# Power_LoadSwitches.net
KiCad netlist of a schematic drawn in Altium Designer
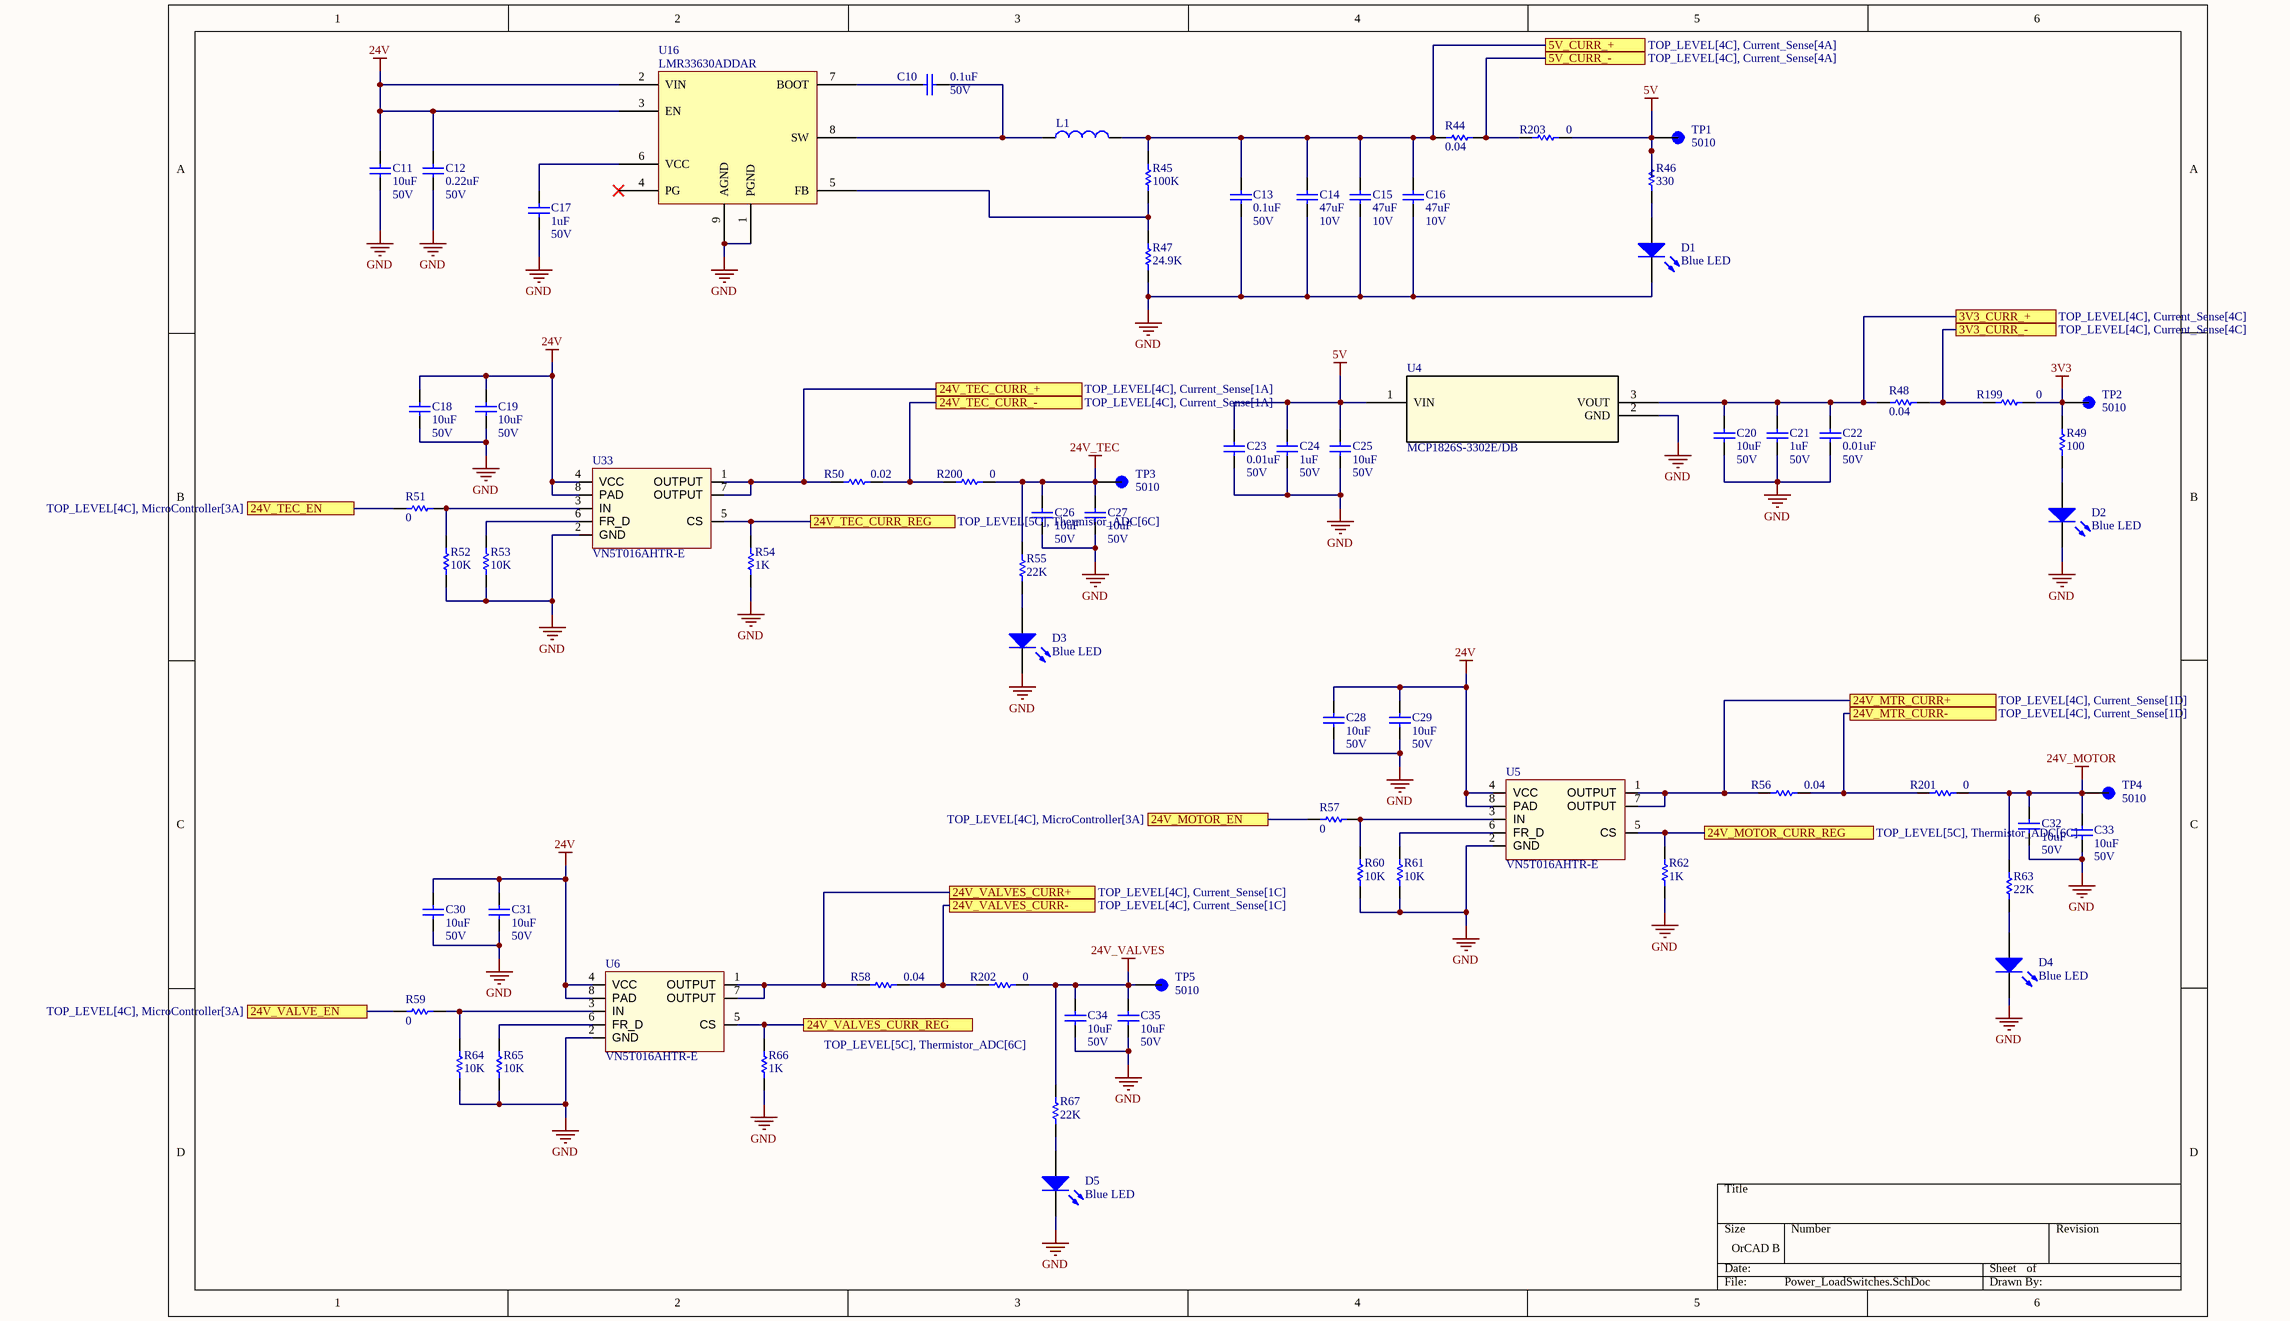
[diagram p0: Power_LoadSwitches.SchDoc]

(export (version "E")
  (design (tool "Eeschema 10.0.6"))
  (components
    (comp (ref "C10")
      (value "0.1uF")
      (footprint "DEFAULT_CAPACITOR_0805")
      (description "CAP CER 0.1UF 50V X7R 0805")
      (fields
        (field (name "MANUFACTURER") "Cal-Chip Electronics, Inc.")
        (field (name "RATING") "50V")
        (field (name "Comment") "KGM21NR71H104KT")
      )
      (libsource (lib "Avery Altium Llibrary") (part "KGM21NR71H104KT"))
    )
    (comp (ref "C11")
      (value "10uF")
      (footprint "DEFAULT_CAPACITOR_0805")
      (description "CAP CER 10UF 50V X5R 0805")
      (fields (field (name "RATING") "50V") (field (name "Comment") "GRM21BR61H106KE43L"))
      (libsource (lib "Avery Altium Llibrary") (part "GRM21BR61H106KE43L"))
    )
    (comp (ref "C12")
      (value "0.22uF")
      (footprint "DEFAULT_CAPACITOR_0805")
      (description "CAP CER 0.22UF 50V X7R 0805")
      (fields (field (name "RATING") "50V") (field (name "Comment") "C0805C224K5RACTU"))
      (libsource (lib "Avery Altium Llibrary") (part "C0805C224K5RACTU"))
    )
    (comp (ref "C13")
      (value "0.1uF")
      (footprint "DEFAULT_CAPACITOR_0805")
      (description "CAP CER 0.1UF 50V X7R 0805")
      (fields
        (field (name "MANUFACTURER") "Cal-Chip Electronics, Inc.")
        (field (name "RATING") "50V")
        (field (name "Comment") "KGM21NR71H104KT")
      )
      (libsource (lib "Avery Altium Llibrary") (part "KGM21NR71H104KT"))
    )
    (comp (ref "C14")
      (value "47uF")
      (footprint "DEFAULT_CAPACITOR_0805")
      (description "CAP CER 47UF 10V X5R 0805")
      (fields (field (name "RATING") "10V") (field (name "Comment") "GRM21BR61A476ME15L"))
      (libsource (lib "Avery Altium Llibrary") (part "GRM21BR61A476ME15L"))
    )
    (comp (ref "C15")
      (value "47uF")
      (footprint "DEFAULT_CAPACITOR_0805")
      (description "CAP CER 47UF 10V X5R 0805")
      (fields (field (name "RATING") "10V") (field (name "Comment") "GRM21BR61A476ME15L"))
      (libsource (lib "Avery Altium Llibrary") (part "GRM21BR61A476ME15L"))
    )
    (comp (ref "C16")
      (value "47uF")
      (footprint "DEFAULT_CAPACITOR_0805")
      (description "CAP CER 47UF 10V X5R 0805")
      (fields (field (name "RATING") "10V") (field (name "Comment") "GRM21BR61A476ME15L"))
      (libsource (lib "Avery Altium Llibrary") (part "GRM21BR61A476ME15L"))
    )
    (comp (ref "C17")
      (value "1uF")
      (footprint "DEFAULT_CAPACITOR_0805")
      (description "CAP CER 1UF 50V X7R 0805")
      (fields (field (name "RATING") "50V") (field (name "Comment") "CL21B105KBFNNNE"))
      (libsource (lib "Avery Altium Llibrary") (part "CL21B105KBFNNNE"))
    )
    (comp (ref "C18")
      (value "10uF")
      (footprint "DEFAULT_CAPACITOR_0805")
      (description "CAP CER 10UF 50V X5R 0805")
      (fields (field (name "RATING") "50V") (field (name "Comment") "GRM21BR61H106KE43L"))
      (libsource (lib "Avery Altium Llibrary") (part "GRM21BR61H106KE43L"))
    )
    (comp (ref "C19")
      (value "10uF")
      (footprint "DEFAULT_CAPACITOR_0805")
      (description "CAP CER 10UF 50V X5R 0805")
      (fields (field (name "RATING") "50V") (field (name "Comment") "GRM21BR61H106KE43L"))
      (libsource (lib "Avery Altium Llibrary") (part "GRM21BR61H106KE43L"))
    )
    (comp (ref "C20")
      (value "10uF")
      (footprint "DEFAULT_CAPACITOR_0805")
      (description "CAP CER 10UF 50V X5R 0805")
      (fields (field (name "RATING") "50V") (field (name "Comment") "GRM21BR61H106KE43L"))
      (libsource (lib "Avery Altium Llibrary") (part "GRM21BR61H106KE43L"))
    )
    (comp (ref "C21")
      (value "1uF")
      (footprint "DEFAULT_CAPACITOR_0805")
      (description "CAP CER 1UF 50V X7R 0805")
      (fields (field (name "RATING") "50V") (field (name "Comment") "CL21B105KBFNNNE"))
      (libsource (lib "Avery Altium Llibrary") (part "CL21B105KBFNNNE"))
    )
    (comp (ref "C22")
      (value "0.01uF")
      (footprint "DEFAULT_CAPACITOR_0805")
      (description "CAP CER 10000PF 50V X7R 0805")
      (fields
        (field (name "MANUFACTURER") "Cal-Chip Electronics, Inc.")
        (field (name "RATING") "50V")
        (field (name "Comment") "KGM21NR71H103KT")
      )
      (libsource (lib "Avery Altium Llibrary") (part "KGM21NR71H103KT"))
    )
    (comp (ref "C23")
      (value "0.01uF")
      (footprint "DEFAULT_CAPACITOR_0805")
      (description "CAP CER 10000PF 50V X7R 0805")
      (fields
        (field (name "MANUFACTURER") "Cal-Chip Electronics, Inc.")
        (field (name "RATING") "50V")
        (field (name "Comment") "KGM21NR71H103KT")
      )
      (libsource (lib "Avery Altium Llibrary") (part "KGM21NR71H103KT"))
    )
    (comp (ref "C24")
      (value "1uF")
      (footprint "DEFAULT_CAPACITOR_0805")
      (description "CAP CER 1UF 50V X7R 0805")
      (fields (field (name "RATING") "50V") (field (name "Comment") "CL21B105KBFNNNE"))
      (libsource (lib "Avery Altium Llibrary") (part "CL21B105KBFNNNE"))
    )
    (comp (ref "C25")
      (value "10uF")
      (footprint "DEFAULT_CAPACITOR_0805")
      (description "CAP CER 10UF 50V X5R 0805")
      (fields (field (name "RATING") "50V") (field (name "Comment") "GRM21BR61H106KE43L"))
      (libsource (lib "Avery Altium Llibrary") (part "GRM21BR61H106KE43L"))
    )
    (comp (ref "C26")
      (value "10uF")
      (footprint "DEFAULT_CAPACITOR_0805")
      (description "CAP CER 10UF 50V X5R 0805")
      (fields (field (name "RATING") "50V") (field (name "Comment") "GRM21BR61H106KE43L"))
      (libsource (lib "Avery Altium Llibrary") (part "GRM21BR61H106KE43L"))
    )
    (comp (ref "C27")
      (value "10uF")
      (footprint "DEFAULT_CAPACITOR_0805")
      (description "CAP CER 10UF 50V X5R 0805")
      (fields (field (name "RATING") "50V") (field (name "Comment") "GRM21BR61H106KE43L"))
      (libsource (lib "Avery Altium Llibrary") (part "GRM21BR61H106KE43L"))
    )
    (comp (ref "C28")
      (value "10uF")
      (footprint "DEFAULT_CAPACITOR_0805")
      (description "CAP CER 10UF 50V X5R 0805")
      (fields (field (name "RATING") "50V") (field (name "Comment") "GRM21BR61H106KE43L"))
      (libsource (lib "Avery Altium Llibrary") (part "GRM21BR61H106KE43L"))
    )
    (comp (ref "C29")
      (value "10uF")
      (footprint "DEFAULT_CAPACITOR_0805")
      (description "CAP CER 10UF 50V X5R 0805")
      (fields (field (name "RATING") "50V") (field (name "Comment") "GRM21BR61H106KE43L"))
      (libsource (lib "Avery Altium Llibrary") (part "GRM21BR61H106KE43L"))
    )
    (comp (ref "C30")
      (value "10uF")
      (footprint "DEFAULT_CAPACITOR_0805")
      (description "CAP CER 10UF 50V X5R 0805")
      (fields (field (name "RATING") "50V") (field (name "Comment") "GRM21BR61H106KE43L"))
      (libsource (lib "Avery Altium Llibrary") (part "GRM21BR61H106KE43L"))
    )
    (comp (ref "C31")
      (value "10uF")
      (footprint "DEFAULT_CAPACITOR_0805")
      (description "CAP CER 10UF 50V X5R 0805")
      (fields (field (name "RATING") "50V") (field (name "Comment") "GRM21BR61H106KE43L"))
      (libsource (lib "Avery Altium Llibrary") (part "GRM21BR61H106KE43L"))
    )
    (comp (ref "C32")
      (value "10uF")
      (footprint "DEFAULT_CAPACITOR_0805")
      (description "CAP CER 10UF 50V X5R 0805")
      (fields (field (name "RATING") "50V") (field (name "Comment") "GRM21BR61H106KE43L"))
      (libsource (lib "Avery Altium Llibrary") (part "GRM21BR61H106KE43L"))
    )
    (comp (ref "C33")
      (value "10uF")
      (footprint "DEFAULT_CAPACITOR_0805")
      (description "CAP CER 10UF 50V X5R 0805")
      (fields (field (name "RATING") "50V") (field (name "Comment") "GRM21BR61H106KE43L"))
      (libsource (lib "Avery Altium Llibrary") (part "GRM21BR61H106KE43L"))
    )
    (comp (ref "C34")
      (value "10uF")
      (footprint "DEFAULT_CAPACITOR_0805")
      (description "CAP CER 10UF 50V X5R 0805")
      (fields (field (name "RATING") "50V") (field (name "Comment") "GRM21BR61H106KE43L"))
      (libsource (lib "Avery Altium Llibrary") (part "GRM21BR61H106KE43L"))
    )
    (comp (ref "C35")
      (value "10uF")
      (footprint "DEFAULT_CAPACITOR_0805")
      (description "CAP CER 10UF 50V X5R 0805")
      (fields (field (name "RATING") "50V") (field (name "Comment") "GRM21BR61H106KE43L"))
      (libsource (lib "Avery Altium Llibrary") (part "GRM21BR61H106KE43L"))
    )
    (comp (ref "D1")
      (value "Blue LED")
      (footprint "DEFAULT_RESISTOR_0805")
      (description "LED BLUE")
      (fields (field (name "MP") "Blue LED 0805") (field (name "Comment") "LSM0805463V"))
      (libsource (lib "Avery Altium Llibrary") (part "LSM0805463V"))
    )
    (comp (ref "D2")
      (value "Blue LED")
      (footprint "DEFAULT_RESISTOR_0805")
      (description "LED BLUE")
      (fields (field (name "MP") "Blue LED 0805") (field (name "Comment") "LSM0805463V"))
      (libsource (lib "Avery Altium Llibrary") (part "LSM0805463V"))
    )
    (comp (ref "D3")
      (value "Blue LED")
      (footprint "DEFAULT_RESISTOR_0805")
      (description "LED BLUE")
      (fields (field (name "MP") "Blue LED 0805") (field (name "Comment") "LSM0805463V"))
      (libsource (lib "Avery Altium Llibrary") (part "LSM0805463V"))
    )
    (comp (ref "D4")
      (value "Blue LED")
      (footprint "DEFAULT_RESISTOR_0805")
      (description "LED BLUE")
      (fields (field (name "MP") "Blue LED 0805") (field (name "Comment") "LSM0805463V"))
      (libsource (lib "Avery Altium Llibrary") (part "LSM0805463V"))
    )
    (comp (ref "D5")
      (value "Blue LED")
      (footprint "DEFAULT_RESISTOR_0805")
      (description "LED BLUE")
      (fields (field (name "MP") "Blue LED 0805") (field (name "Comment") "LSM0805463V"))
      (libsource (lib "Avery Altium Llibrary") (part "LSM0805463V"))
    )
    (comp (ref "L1")
      (value "744771008")
      (footprint "744771008")
      (description "FIXED IND 8.2UH 6.25A 20 MOHM")
      (libsource (lib "Avery Altium Llibrary") (part "744771008"))
    )
    (comp (ref "R44")
      (value "0.04")
      (footprint "DEFAULT_RESISTOR_0805")
      (description "RES 0.04 OHM 0.5% 1/2W 0805")
      (fields (field (name "POWER") "1/2W") (field (name "TOLERANCE") "0.5%"))
      (libsource (lib "Avery Altium Llibrary") (part "WSLP0805R0400DEA"))
    )
    (comp (ref "R45")
      (value "100K")
      (footprint "DEFAULT_RESISTOR_0805")
      (description "RES 100K OHM 1% 1/8W 0805")
      (fields (field (name "POWER") "1/8W") (field (name "TOLERANCE") "1%"))
      (libsource (lib "Avery Altium Llibrary") (part "RC0805FR-07100KL"))
    )
    (comp (ref "R46")
      (value "330")
      (footprint "DEFAULT_RESISTOR_0805")
      (description "RES 330 OHM 1% 1/8W 0805")
      (fields (field (name "TOLERANCE") "1%") (field (name "Comment") "RMCF0805FT330R"))
      (libsource (lib "Avery Altium Llibrary") (part "RMCF0805FT330R"))
    )
    (comp (ref "R47")
      (value "24.9K")
      (footprint "DEFAULT_RESISTOR_0805")
      (description "RES 24.9K OHM 1% 1/8W 0805")
      (fields (field (name "POWER") "1/8W") (field (name "TOLERANCE") "1%"))
      (libsource (lib "Avery Altium Llibrary") (part "RMCF0805FT24K9"))
    )
    (comp (ref "R48")
      (value "0.04")
      (footprint "DEFAULT_RESISTOR_0805")
      (description "RES 0.04 OHM 0.5% 1/2W 0805")
      (fields (field (name "POWER") "1/2W") (field (name "TOLERANCE") "0.5%"))
      (libsource (lib "Avery Altium Llibrary") (part "WSLP0805R0400DEA"))
    )
    (comp (ref "R49")
      (value "100")
      (footprint "DEFAULT_RESISTOR_0805")
      (description "RES SMD 100 OHM 1% 1/4W 0805")
      (fields (field (name "POWER") "1/4W") (field (name "TOLERANCE") "1%"))
      (libsource (lib "Avery Altium Llibrary") (part "CRCW0805100RFKEA"))
    )
    (comp (ref "R50")
      (value "0.02")
      (footprint "DEFAULT_RESISTOR_0805")
      (description "RES 0.02 OHM 0.5% 1/2W 0805")
      (fields (field (name "POWER") "1/2W") (field (name "TOLERANCE") "0.5%"))
      (libsource (lib "Avery Altium Llibrary") (part "ERJ-6CWDR020V"))
    )
    (comp (ref "R51")
      (value "0")
      (footprint "DEFAULT_RESISTOR_0805")
      (description "RES 0 OHM JUMPER 1/8W 0805")
      (fields (field (name "POWER") "1/8W") (field (name "Comment") "RC0805JR-070RL"))
      (libsource (lib "Avery Altium Llibrary") (part "RC0805JR-070RL"))
    )
    (comp (ref "R52")
      (value "10K")
      (footprint "DEFAULT_RESISTOR_0805")
      (description "RES SMD 10K OHM 1% 1/4W 0805")
      (fields (field (name "POWER") "1/4W") (field (name "TOLERANCE") "1%"))
      (libsource (lib "Avery Altium Llibrary") (part "CRCW080510K0FKEA"))
    )
    (comp (ref "R53")
      (value "10K")
      (footprint "DEFAULT_RESISTOR_0805")
      (description "RES SMD 10K OHM 1% 1/4W 0805")
      (fields (field (name "POWER") "1/4W") (field (name "TOLERANCE") "1%"))
      (libsource (lib "Avery Altium Llibrary") (part "CRCW080510K0FKEA"))
    )
    (comp (ref "R54")
      (value "1K")
      (footprint "DEFAULT_RESISTOR_0805")
      (description "RES SMD 1K OHM 1% 1/4W 0805")
      (fields (field (name "POWER") "1/4W") (field (name "TOLERANCE") "1%"))
      (libsource (lib "Avery Altium Llibrary") (part "CRCW08051K00FKEA"))
    )
    (comp (ref "R55")
      (value "22K")
      (footprint "DEFAULT_RESISTOR_0805")
      (description "RES 22K OHM 1% 1/8W 0805")
      (fields (field (name "POWER") "1/8W") (field (name "TOLERANCE") "1%"))
      (libsource (lib "Avery Altium Llibrary") (part "RC0805FR-1322KL"))
    )
    (comp (ref "R56")
      (value "0.04")
      (footprint "DEFAULT_RESISTOR_0805")
      (description "RES 0.04 OHM 0.5% 1/2W 0805")
      (fields (field (name "POWER") "1/2W") (field (name "TOLERANCE") "0.5%"))
      (libsource (lib "Avery Altium Llibrary") (part "WSLP0805R0400DEA"))
    )
    (comp (ref "R57")
      (value "0")
      (footprint "DEFAULT_RESISTOR_0805")
      (description "RES 0 OHM JUMPER 1/8W 0805")
      (fields (field (name "POWER") "1/8W") (field (name "Comment") "RC0805JR-070RL"))
      (libsource (lib "Avery Altium Llibrary") (part "RC0805JR-070RL"))
    )
    (comp (ref "R58")
      (value "0.04")
      (footprint "DEFAULT_RESISTOR_0805")
      (description "RES 0.04 OHM 0.5% 1/2W 0805")
      (fields (field (name "POWER") "1/2W") (field (name "TOLERANCE") "0.5%"))
      (libsource (lib "Avery Altium Llibrary") (part "WSLP0805R0400DEA"))
    )
    (comp (ref "R59")
      (value "0")
      (footprint "DEFAULT_RESISTOR_0805")
      (description "RES 0 OHM JUMPER 1/8W 0805")
      (fields (field (name "POWER") "1/8W") (field (name "Comment") "RC0805JR-070RL"))
      (libsource (lib "Avery Altium Llibrary") (part "RC0805JR-070RL"))
    )
    (comp (ref "R60")
      (value "10K")
      (footprint "DEFAULT_RESISTOR_0805")
      (description "RES SMD 10K OHM 1% 1/4W 0805")
      (fields (field (name "POWER") "1/4W") (field (name "TOLERANCE") "1%"))
      (libsource (lib "Avery Altium Llibrary") (part "CRCW080510K0FKEA"))
    )
    (comp (ref "R61")
      (value "10K")
      (footprint "DEFAULT_RESISTOR_0805")
      (description "RES SMD 10K OHM 1% 1/4W 0805")
      (fields (field (name "POWER") "1/4W") (field (name "TOLERANCE") "1%"))
      (libsource (lib "Avery Altium Llibrary") (part "CRCW080510K0FKEA"))
    )
    (comp (ref "R62")
      (value "1K")
      (footprint "DEFAULT_RESISTOR_0805")
      (description "RES SMD 1K OHM 1% 1/4W 0805")
      (fields (field (name "POWER") "1/4W") (field (name "TOLERANCE") "1%"))
      (libsource (lib "Avery Altium Llibrary") (part "CRCW08051K00FKEA"))
    )
    (comp (ref "R63")
      (value "22K")
      (footprint "DEFAULT_RESISTOR_0805")
      (description "RES 22K OHM 1% 1/8W 0805")
      (fields (field (name "POWER") "1/8W") (field (name "TOLERANCE") "1%"))
      (libsource (lib "Avery Altium Llibrary") (part "RC0805FR-1322KL"))
    )
    (comp (ref "R64")
      (value "10K")
      (footprint "DEFAULT_RESISTOR_0805")
      (description "RES SMD 10K OHM 1% 1/4W 0805")
      (fields (field (name "POWER") "1/4W") (field (name "TOLERANCE") "1%"))
      (libsource (lib "Avery Altium Llibrary") (part "CRCW080510K0FKEA"))
    )
    (comp (ref "R65")
      (value "10K")
      (footprint "DEFAULT_RESISTOR_0805")
      (description "RES SMD 10K OHM 1% 1/4W 0805")
      (fields (field (name "POWER") "1/4W") (field (name "TOLERANCE") "1%"))
      (libsource (lib "Avery Altium Llibrary") (part "CRCW080510K0FKEA"))
    )
    (comp (ref "R66")
      (value "1K")
      (footprint "DEFAULT_RESISTOR_0805")
      (description "RES SMD 1K OHM 1% 1/4W 0805")
      (fields (field (name "POWER") "1/4W") (field (name "TOLERANCE") "1%"))
      (libsource (lib "Avery Altium Llibrary") (part "CRCW08051K00FKEA"))
    )
    (comp (ref "R67")
      (value "22K")
      (footprint "DEFAULT_RESISTOR_0805")
      (description "RES 22K OHM 1% 1/8W 0805")
      (fields (field (name "POWER") "1/8W") (field (name "TOLERANCE") "1%"))
      (libsource (lib "Avery Altium Llibrary") (part "RC0805FR-1322KL"))
    )
    (comp (ref "R199")
      (value "0")
      (footprint "DEFAULT_RESISTOR_0805")
      (description "RES 0 OHM JUMPER 1/8W 0805")
      (fields (field (name "POWER") "1/8W") (field (name "Comment") "RC0805JR-070RL"))
      (libsource (lib "Avery Altium Llibrary") (part "RC0805JR-070RL"))
    )
    (comp (ref "R200")
      (value "0")
      (footprint "DEFAULT_RESISTOR_0805")
      (description "RES 0 OHM JUMPER 1/8W 0805")
      (fields (field (name "POWER") "1/8W") (field (name "Comment") "RC0805JR-070RL"))
      (libsource (lib "Avery Altium Llibrary") (part "RC0805JR-070RL"))
    )
    (comp (ref "R201")
      (value "0")
      (footprint "DEFAULT_RESISTOR_0805")
      (description "RES 0 OHM JUMPER 1/8W 0805")
      (fields (field (name "POWER") "1/8W") (field (name "Comment") "RC0805JR-070RL"))
      (libsource (lib "Avery Altium Llibrary") (part "RC0805JR-070RL"))
    )
    (comp (ref "R202")
      (value "0")
      (footprint "DEFAULT_RESISTOR_0805")
      (description "RES 0 OHM JUMPER 1/8W 0805")
      (fields (field (name "POWER") "1/8W") (field (name "Comment") "RC0805JR-070RL"))
      (libsource (lib "Avery Altium Llibrary") (part "RC0805JR-070RL"))
    )
    (comp (ref "R203")
      (value "0")
      (footprint "DEFAULT_RESISTOR_0805")
      (description "RES 0 OHM JUMPER 1/8W 0805")
      (fields (field (name "POWER") "1/8W") (field (name "Comment") "RC0805JR-070RL"))
      (libsource (lib "Avery Altium Llibrary") (part "RC0805JR-070RL"))
    )
    (comp (ref "TP1")
      (value "5010")
      (footprint "TP_5011")
      (description "PC TEST POINT MULTIPURPOSE RED")
      (libsource (lib "Avery Altium Llibrary") (part "5010"))
    )
    (comp (ref "TP2")
      (value "5010")
      (footprint "TP_5011")
      (description "PC TEST POINT MULTIPURPOSE RED")
      (libsource (lib "Avery Altium Llibrary") (part "5010"))
    )
    (comp (ref "TP3")
      (value "5010")
      (footprint "TP_5011")
      (description "PC TEST POINT MULTIPURPOSE RED")
      (libsource (lib "Avery Altium Llibrary") (part "5010"))
    )
    (comp (ref "TP4")
      (value "5010")
      (footprint "TP_5011")
      (description "PC TEST POINT MULTIPURPOSE RED")
      (libsource (lib "Avery Altium Llibrary") (part "5010"))
    )
    (comp (ref "TP5")
      (value "5010")
      (footprint "TP_5011")
      (description "PC TEST POINT MULTIPURPOSE RED")
      (libsource (lib "Avery Altium Llibrary") (part "5010"))
    )
    (comp (ref "U4")
      (value "MCP1826S-3302E/DB")
      (footprint "MCP1826S-3302E/DB")
      (description "IC REG LINEAR 3.3V 1A SOT-223-3")
      (fields (field (name "COPYRIGHT") "Copyright (C) 2025 Ultra Librarian. All rights reserved."))
      (libsource (lib "Avery Altium Llibrary") (part "MCP1826S-3302E/DB"))
    )
    (comp (ref "U5")
      (value "VN5T016AHTR-E")
      (footprint "VN5T016AHTR-E-HPAK")
      (description "Power Switch/Driver 1:1 N-Channel 43A HPAK")
      (fields
        (field (name "MANUFACTURER") "STMicroelectronics")
        (field (name "MANUFACTURER P/N") "VN5T016AHTR-E")
      )
      (libsource (lib "Avery Schem Library") (part "VN5T016AHTR-E"))
    )
    (comp (ref "U6")
      (value "VN5T016AHTR-E")
      (footprint "VN5T016AHTR-E-HPAK")
      (description "Power Switch/Driver 1:1 N-Channel 43A HPAK")
      (fields
        (field (name "MANUFACTURER") "STMicroelectronics")
        (field (name "MANUFACTURER P/N") "VN5T016AHTR-E")
      )
      (libsource (lib "Avery Schem Library") (part "VN5T016AHTR-E"))
    )
    (comp (ref "U16")
      (value "LMR33630ADDAR")
      (footprint "VREG_LM5017MR/NOPB")
      (description "LMR33630 SIMPLE SWITCHER® 3.8-V to 36-V, 3-A\r\nSynchronous Step-down Voltage Converter")
      (fields (field (name "MP") "LMR33630ADDA") (field (name "DESIGNER") "OMIGA"))
      (libsource (lib "Avery Altium Llibrary") (part "LMR33630ADDAR"))
    )
    (comp (ref "U33")
      (value "VN5T016AHTR-E")
      (footprint "VN5T016AHTR-E-HPAK")
      (description "Power Switch/Driver 1:1 N-Channel 43A HPAK")
      (fields
        (field (name "MANUFACTURER") "STMicroelectronics")
        (field (name "MANUFACTURER P/N") "VN5T016AHTR-E")
      )
      (libsource (lib "Avery Schem Library") (part "VN5T016AHTR-E"))
    )
  )
  (nets
    (net (code "1") (name "/3V3_CURR_+") (class "Default")
      (node (ref "C20") (pin "2") (pinfunction "2_2") (pintype "passive"))
      (node (ref "C21") (pin "2") (pinfunction "2_2") (pintype "passive"))
      (node (ref "C22") (pin "2") (pinfunction "2_2") (pintype "passive"))
      (node (ref "R48") (pin "2") (pinfunction "2_2") (pintype "passive"))
      (node (ref "U4") (pin "3") (pinfunction "VOUT_3") (pintype "passive"))
    )
    (net (code "2") (name "/3V3_CURR_-") (class "Default")
      (node (ref "R199") (pin "2") (pinfunction "2_2") (pintype "passive"))
      (node (ref "R48") (pin "1") (pinfunction "1_1") (pintype "passive"))
    )
    (net (code "3") (name "/5V_CURR_+") (class "Default")
      (node (ref "C13") (pin "2") (pinfunction "2_2") (pintype "passive"))
      (node (ref "C14") (pin "2") (pinfunction "2_2") (pintype "passive"))
      (node (ref "C15") (pin "2") (pinfunction "2_2") (pintype "passive"))
      (node (ref "C16") (pin "2") (pinfunction "2_2") (pintype "passive"))
      (node (ref "L1") (pin "2") (pinfunction "2_2") (pintype "passive"))
      (node (ref "R44") (pin "2") (pinfunction "2_2") (pintype "passive"))
      (node (ref "R45") (pin "1") (pinfunction "1_1") (pintype "passive"))
    )
    (net (code "4") (name "/5V_CURR_-") (class "Default")
      (node (ref "R203") (pin "2") (pinfunction "2_2") (pintype "passive"))
      (node (ref "R44") (pin "1") (pinfunction "1_1") (pintype "passive"))
    )
    (net (code "5") (name "/24V_MOTOR_CURR_REG") (class "Default")
      (node (ref "R62") (pin "1") (pinfunction "1_1") (pintype "passive"))
      (node (ref "U5") (pin "5") (pinfunction "CS_5") (pintype "passive"))
    )
    (net (code "6") (name "/24V_MOTOR_EN") (class "Default")
      (node (ref "R57") (pin "2") (pinfunction "2_2") (pintype "passive"))
    )
    (net (code "7") (name "/24V_MTR_CURR+") (class "Default")
      (node (ref "R56") (pin "2") (pinfunction "2_2") (pintype "passive"))
      (node (ref "U5") (pin "1") (pinfunction "OUTPUT_1") (pintype "passive"))
      (node (ref "U5") (pin "7") (pinfunction "OUTPUT_7") (pintype "passive"))
    )
    (net (code "8") (name "/24V_MTR_CURR-") (class "Default")
      (node (ref "R201") (pin "2") (pinfunction "2_2") (pintype "passive"))
      (node (ref "R56") (pin "1") (pinfunction "1_1") (pintype "passive"))
    )
    (net (code "9") (name "/24V_TEC_CURR_+") (class "Default")
      (node (ref "R50") (pin "2") (pinfunction "2_2") (pintype "passive"))
      (node (ref "U33") (pin "1") (pinfunction "OUTPUT_1") (pintype "passive"))
      (node (ref "U33") (pin "7") (pinfunction "OUTPUT_7") (pintype "passive"))
    )
    (net (code "10") (name "/24V_TEC_CURR_-") (class "Default")
      (node (ref "R200") (pin "2") (pinfunction "2_2") (pintype "passive"))
      (node (ref "R50") (pin "1") (pinfunction "1_1") (pintype "passive"))
    )
    (net (code "11") (name "/24V_TEC_CURR_REG") (class "Default")
      (node (ref "R54") (pin "1") (pinfunction "1_1") (pintype "passive"))
      (node (ref "U33") (pin "5") (pinfunction "CS_5") (pintype "passive"))
    )
    (net (code "12") (name "/24V_TEC_EN") (class "Default")
      (node (ref "R51") (pin "2") (pinfunction "2_2") (pintype "passive"))
    )
    (net (code "13") (name "/24V_VALVES_CURR+") (class "Default")
      (node (ref "R58") (pin "2") (pinfunction "2_2") (pintype "passive"))
      (node (ref "U6") (pin "1") (pinfunction "OUTPUT_1") (pintype "passive"))
      (node (ref "U6") (pin "7") (pinfunction "OUTPUT_7") (pintype "passive"))
    )
    (net (code "14") (name "/24V_VALVES_CURR-") (class "Default")
      (node (ref "R202") (pin "2") (pinfunction "2_2") (pintype "passive"))
      (node (ref "R58") (pin "1") (pinfunction "1_1") (pintype "passive"))
    )
    (net (code "15") (name "/24V_VALVES_CURR_REG") (class "Default")
      (node (ref "R66") (pin "1") (pinfunction "1_1") (pintype "passive"))
      (node (ref "U6") (pin "5") (pinfunction "CS_5") (pintype "passive"))
    )
    (net (code "16") (name "/24V_VALVE_EN") (class "Default")
      (node (ref "R59") (pin "2") (pinfunction "2_2") (pintype "passive"))
    )
    (net (code "17") (name "3V3") (class "Default")
      (node (ref "R199") (pin "1") (pinfunction "1_1") (pintype "passive"))
      (node (ref "R49") (pin "1") (pinfunction "1_1") (pintype "passive"))
      (node (ref "TP2") (pin "TP") (pinfunction "TP_TP") (pintype "passive"))
    )
    (net (code "18") (name "5V") (class "Default")
      (node (ref "C23") (pin "2") (pinfunction "2_2") (pintype "passive"))
      (node (ref "C24") (pin "2") (pinfunction "2_2") (pintype "passive"))
      (node (ref "C25") (pin "2") (pinfunction "2_2") (pintype "passive"))
      (node (ref "R203") (pin "1") (pinfunction "1_1") (pintype "passive"))
      (node (ref "R46") (pin "1") (pinfunction "1_1") (pintype "passive"))
      (node (ref "TP1") (pin "TP") (pinfunction "TP_TP") (pintype "passive"))
      (node (ref "U4") (pin "1") (pinfunction "VIN_1") (pintype "passive"))
    )
    (net (code "19") (name "24V") (class "Default")
      (node (ref "C11") (pin "2") (pinfunction "2_2") (pintype "passive"))
      (node (ref "C12") (pin "2") (pinfunction "2_2") (pintype "passive"))
      (node (ref "C18") (pin "2") (pinfunction "2_2") (pintype "passive"))
      (node (ref "C19") (pin "2") (pinfunction "2_2") (pintype "passive"))
      (node (ref "C28") (pin "2") (pinfunction "2_2") (pintype "passive"))
      (node (ref "C29") (pin "2") (pinfunction "2_2") (pintype "passive"))
      (node (ref "C30") (pin "2") (pinfunction "2_2") (pintype "passive"))
      (node (ref "C31") (pin "2") (pinfunction "2_2") (pintype "passive"))
      (node (ref "U16") (pin "2") (pinfunction "VIN_2") (pintype "power_in"))
      (node (ref "U16") (pin "3") (pinfunction "EN_3") (pintype "passive"))
      (node (ref "U33") (pin "4") (pinfunction "VCC_4") (pintype "passive"))
      (node (ref "U33") (pin "8") (pinfunction "PAD_8") (pintype "passive"))
      (node (ref "U5") (pin "4") (pinfunction "VCC_4") (pintype "passive"))
      (node (ref "U5") (pin "8") (pinfunction "PAD_8") (pintype "passive"))
      (node (ref "U6") (pin "4") (pinfunction "VCC_4") (pintype "passive"))
      (node (ref "U6") (pin "8") (pinfunction "PAD_8") (pintype "passive"))
    )
    (net (code "20") (name "24V_MOTOR") (class "Default")
      (node (ref "C32") (pin "2") (pinfunction "2_2") (pintype "passive"))
      (node (ref "C33") (pin "2") (pinfunction "2_2") (pintype "passive"))
      (node (ref "R201") (pin "1") (pinfunction "1_1") (pintype "passive"))
      (node (ref "R63") (pin "1") (pinfunction "1_1") (pintype "passive"))
      (node (ref "TP4") (pin "TP") (pinfunction "TP_TP") (pintype "passive"))
    )
    (net (code "21") (name "24V_TEC") (class "Default")
      (node (ref "C26") (pin "2") (pinfunction "2_2") (pintype "passive"))
      (node (ref "C27") (pin "2") (pinfunction "2_2") (pintype "passive"))
      (node (ref "R200") (pin "1") (pinfunction "1_1") (pintype "passive"))
      (node (ref "R55") (pin "1") (pinfunction "1_1") (pintype "passive"))
      (node (ref "TP3") (pin "TP") (pinfunction "TP_TP") (pintype "passive"))
    )
    (net (code "22") (name "24V_VALVES") (class "Default")
      (node (ref "C34") (pin "2") (pinfunction "2_2") (pintype "passive"))
      (node (ref "C35") (pin "2") (pinfunction "2_2") (pintype "passive"))
      (node (ref "R202") (pin "1") (pinfunction "1_1") (pintype "passive"))
      (node (ref "R67") (pin "1") (pinfunction "1_1") (pintype "passive"))
      (node (ref "TP5") (pin "TP") (pinfunction "TP_TP") (pintype "passive"))
    )
    (net (code "23") (name "GND") (class "Default")
      (node (ref "C11") (pin "1") (pinfunction "1_1") (pintype "passive"))
      (node (ref "C12") (pin "1") (pinfunction "1_1") (pintype "passive"))
      (node (ref "C13") (pin "1") (pinfunction "1_1") (pintype "passive"))
      (node (ref "C14") (pin "1") (pinfunction "1_1") (pintype "passive"))
      (node (ref "C15") (pin "1") (pinfunction "1_1") (pintype "passive"))
      (node (ref "C16") (pin "1") (pinfunction "1_1") (pintype "passive"))
      (node (ref "C17") (pin "1") (pinfunction "1_1") (pintype "passive"))
      (node (ref "C18") (pin "1") (pinfunction "1_1") (pintype "passive"))
      (node (ref "C19") (pin "1") (pinfunction "1_1") (pintype "passive"))
      (node (ref "C20") (pin "1") (pinfunction "1_1") (pintype "passive"))
      (node (ref "C21") (pin "1") (pinfunction "1_1") (pintype "passive"))
      (node (ref "C22") (pin "1") (pinfunction "1_1") (pintype "passive"))
      (node (ref "C23") (pin "1") (pinfunction "1_1") (pintype "passive"))
      (node (ref "C24") (pin "1") (pinfunction "1_1") (pintype "passive"))
      (node (ref "C25") (pin "1") (pinfunction "1_1") (pintype "passive"))
      (node (ref "C26") (pin "1") (pinfunction "1_1") (pintype "passive"))
      (node (ref "C27") (pin "1") (pinfunction "1_1") (pintype "passive"))
      (node (ref "C28") (pin "1") (pinfunction "1_1") (pintype "passive"))
      (node (ref "C29") (pin "1") (pinfunction "1_1") (pintype "passive"))
      (node (ref "C30") (pin "1") (pinfunction "1_1") (pintype "passive"))
      (node (ref "C31") (pin "1") (pinfunction "1_1") (pintype "passive"))
      (node (ref "C32") (pin "1") (pinfunction "1_1") (pintype "passive"))
      (node (ref "C33") (pin "1") (pinfunction "1_1") (pintype "passive"))
      (node (ref "C34") (pin "1") (pinfunction "1_1") (pintype "passive"))
      (node (ref "C35") (pin "1") (pinfunction "1_1") (pintype "passive"))
      (node (ref "D1") (pin "2") (pinfunction "K_2") (pintype "passive"))
      (node (ref "D2") (pin "2") (pinfunction "K_2") (pintype "passive"))
      (node (ref "D3") (pin "2") (pinfunction "K_2") (pintype "passive"))
      (node (ref "D4") (pin "2") (pinfunction "K_2") (pintype "passive"))
      (node (ref "D5") (pin "2") (pinfunction "K_2") (pintype "passive"))
      (node (ref "R47") (pin "2") (pinfunction "2_2") (pintype "passive"))
      (node (ref "R52") (pin "2") (pinfunction "2_2") (pintype "passive"))
      (node (ref "R53") (pin "2") (pinfunction "2_2") (pintype "passive"))
      (node (ref "R54") (pin "2") (pinfunction "2_2") (pintype "passive"))
      (node (ref "R60") (pin "2") (pinfunction "2_2") (pintype "passive"))
      (node (ref "R61") (pin "2") (pinfunction "2_2") (pintype "passive"))
      (node (ref "R62") (pin "2") (pinfunction "2_2") (pintype "passive"))
      (node (ref "R64") (pin "2") (pinfunction "2_2") (pintype "passive"))
      (node (ref "R65") (pin "2") (pinfunction "2_2") (pintype "passive"))
      (node (ref "R66") (pin "2") (pinfunction "2_2") (pintype "passive"))
      (node (ref "U16") (pin "1") (pinfunction "PGND_1") (pintype "passive"))
      (node (ref "U16") (pin "9") (pinfunction "AGND_9") (pintype "passive"))
      (node (ref "U33") (pin "2") (pinfunction "GND_2") (pintype "passive"))
      (node (ref "U4") (pin "2") (pinfunction "GND_2") (pintype "passive"))
      (node (ref "U5") (pin "2") (pinfunction "GND_2") (pintype "passive"))
      (node (ref "U6") (pin "2") (pinfunction "GND_2") (pintype "passive"))
    )
    (net (code "24") (name "Net-(D1-A)") (class "Default")
      (node (ref "D1") (pin "1") (pinfunction "A_1") (pintype "passive"))
      (node (ref "R46") (pin "2") (pinfunction "2_2") (pintype "passive"))
    )
    (net (code "25") (name "Net-(D2-A)") (class "Default")
      (node (ref "D2") (pin "1") (pinfunction "A_1") (pintype "passive"))
      (node (ref "R49") (pin "2") (pinfunction "2_2") (pintype "passive"))
    )
    (net (code "26") (name "Net-(D3-A)") (class "Default")
      (node (ref "D3") (pin "1") (pinfunction "A_1") (pintype "passive"))
      (node (ref "R55") (pin "2") (pinfunction "2_2") (pintype "passive"))
    )
    (net (code "27") (name "Net-(D4-A)") (class "Default")
      (node (ref "D4") (pin "1") (pinfunction "A_1") (pintype "passive"))
      (node (ref "R63") (pin "2") (pinfunction "2_2") (pintype "passive"))
    )
    (net (code "28") (name "Net-(D5-A)") (class "Default")
      (node (ref "D5") (pin "1") (pinfunction "A_1") (pintype "passive"))
      (node (ref "R67") (pin "2") (pinfunction "2_2") (pintype "passive"))
    )
    (net (code "29") (name "Net-(U5-FR_D)") (class "Default")
      (node (ref "R61") (pin "1") (pinfunction "1_1") (pintype "passive"))
      (node (ref "U5") (pin "6") (pinfunction "FR_D_6") (pintype "passive"))
    )
    (net (code "30") (name "Net-(U5-IN)") (class "Default")
      (node (ref "R57") (pin "1") (pinfunction "1_1") (pintype "passive"))
      (node (ref "R60") (pin "1") (pinfunction "1_1") (pintype "passive"))
      (node (ref "U5") (pin "3") (pinfunction "IN_3") (pintype "passive"))
    )
    (net (code "31") (name "Net-(U6-FR_D)") (class "Default")
      (node (ref "R65") (pin "1") (pinfunction "1_1") (pintype "passive"))
      (node (ref "U6") (pin "6") (pinfunction "FR_D_6") (pintype "passive"))
    )
    (net (code "32") (name "Net-(U6-IN)") (class "Default")
      (node (ref "R59") (pin "1") (pinfunction "1_1") (pintype "passive"))
      (node (ref "R64") (pin "1") (pinfunction "1_1") (pintype "passive"))
      (node (ref "U6") (pin "3") (pinfunction "IN_3") (pintype "passive"))
    )
    (net (code "33") (name "Net-(U16-BOOT)") (class "Default")
      (node (ref "C10") (pin "2") (pinfunction "2_2") (pintype "passive"))
      (node (ref "U16") (pin "7") (pinfunction "BOOT_7") (pintype "passive"))
    )
    (net (code "34") (name "Net-(U16-FB)") (class "Default")
      (node (ref "R45") (pin "2") (pinfunction "2_2") (pintype "passive"))
      (node (ref "R47") (pin "1") (pinfunction "1_1") (pintype "passive"))
      (node (ref "U16") (pin "5") (pinfunction "FB_5") (pintype "passive"))
    )
    (net (code "35") (name "Net-(U16-SW)") (class "Default")
      (node (ref "C10") (pin "1") (pinfunction "1_1") (pintype "passive"))
      (node (ref "L1") (pin "1") (pinfunction "1_1") (pintype "passive"))
      (node (ref "U16") (pin "8") (pinfunction "SW_8") (pintype "passive"))
    )
    (net (code "36") (name "Net-(U16-VCC)") (class "Default")
      (node (ref "C17") (pin "2") (pinfunction "2_2") (pintype "passive"))
      (node (ref "U16") (pin "6") (pinfunction "VCC_6") (pintype "passive"))
    )
    (net (code "37") (name "Net-(U33-FR_D)") (class "Default")
      (node (ref "R53") (pin "1") (pinfunction "1_1") (pintype "passive"))
      (node (ref "U33") (pin "6") (pinfunction "FR_D_6") (pintype "passive"))
    )
    (net (code "38") (name "Net-(U33-IN)") (class "Default")
      (node (ref "R51") (pin "1") (pinfunction "1_1") (pintype "passive"))
      (node (ref "R52") (pin "1") (pinfunction "1_1") (pintype "passive"))
      (node (ref "U33") (pin "3") (pinfunction "IN_3") (pintype "passive"))
    )
    (net (code "39") (name "unconnected-(U16-PG-Pad4)") (class "Default")
      (node (ref "U16") (pin "4") (pinfunction "PG_4") (pintype "passive+no_connect"))
    )
  )
)
